# SCH003.net
KiCad netlist of a schematic drawn in Altium Designer
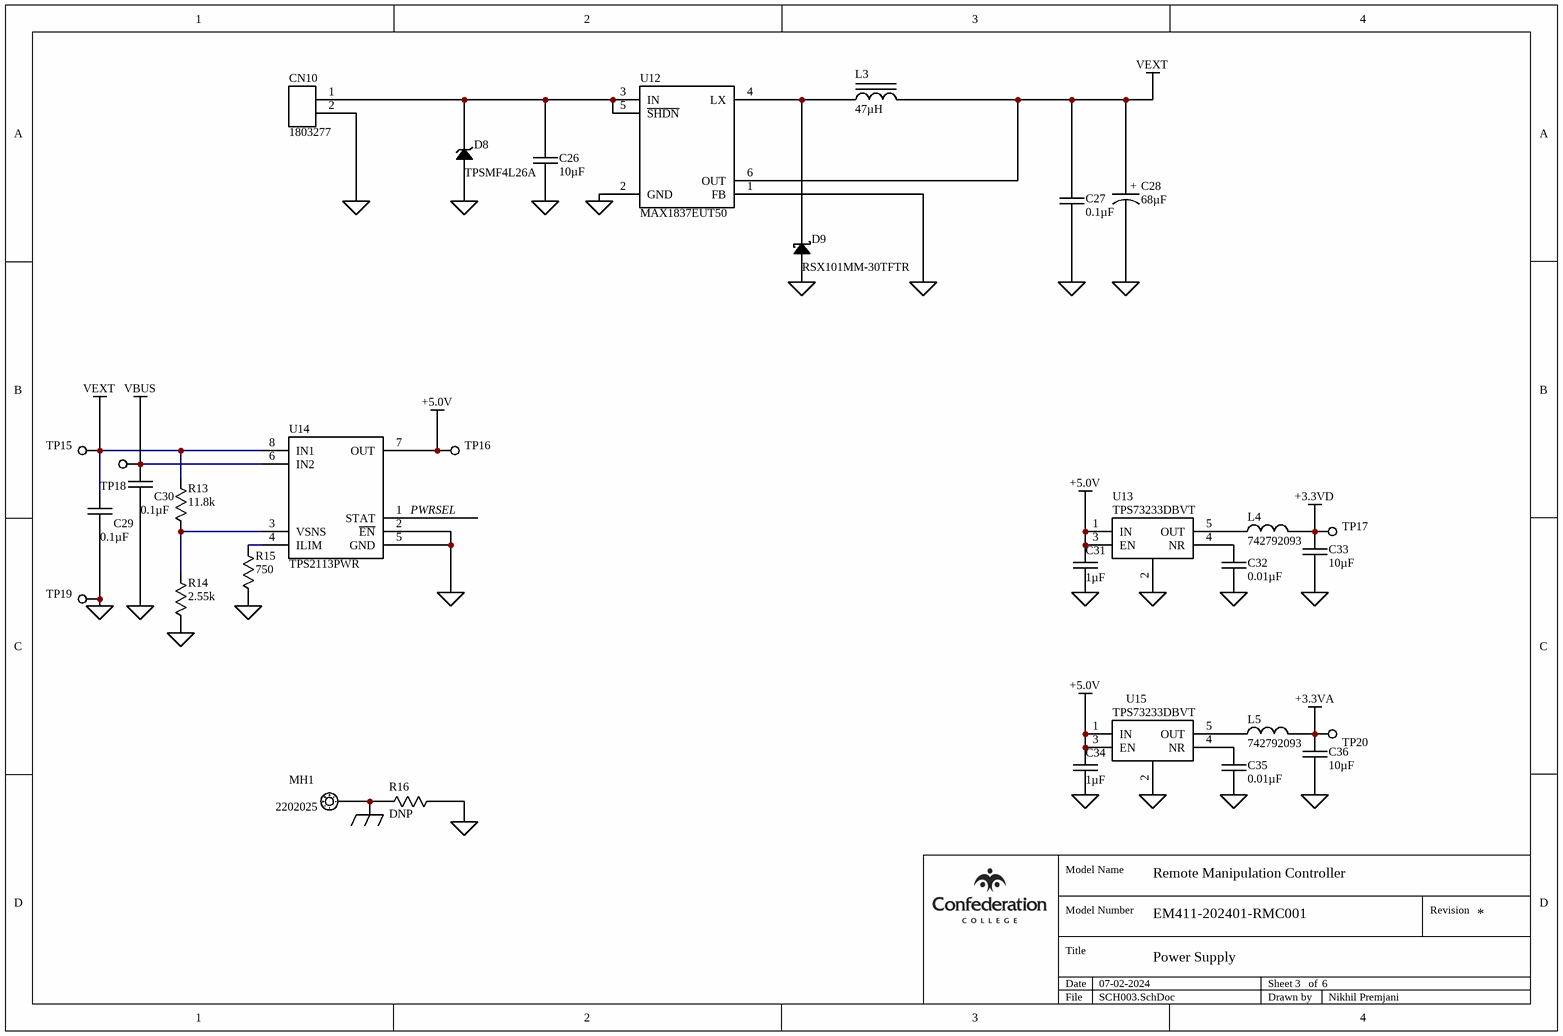
[diagram p0: SCH003.SchDoc]

(export (version "E")
  (design (tool "Eeschema 10.0.6"))
  (components
    (comp (ref "C26")
      (value "10µF")
      (footprint "CAPC2012X14N")
      (description "10µF/25V 10% X5R Multi-Layer Ceramic Capacitor")
      (fields
        (field (name "MANUFACTURER") "Samsung Electro-Mechanics")
        (field (name "PARTNUMBER") "CL21A106KAFN3NE")
      )
      (libsource (lib "EM411-202401-RMC001-000-20240213-T10") (part "CL21A106KAFN3NE"))
    )
    (comp (ref "C27")
      (value "0.1µF")
      (footprint "CAPC2012X14N")
      (description "0.1µF/50V/±10% X7R Ceramic Chip Capacitor")
      (fields (field (name "MANUFACTURER") "Taiyo Yuden") (field (name "PARTNUMBER") "UMK212B7104KGHT"))
      (libsource (lib "EM411-202401-RMC001-001") (part "UMK212B7104KGHT"))
    )
    (comp (ref "C28")
      (value "68µF")
      (footprint "CAPAE7366X60M")
      (description "68µF/10V/20% SMD Aluminum Conductive Polymer Electrolytic Capacitor")
      (fields (field (name "MANUFACTURER") "AVX") (field (name "PARTNUMBER") "APA0606680M010R"))
      (libsource (lib "EM411-202401-RMC001-000-20240213-T10") (part "APA0606680M010R"))
    )
    (comp (ref "C29")
      (value "0.1µF")
      (footprint "CAPC2012X14N")
      (description "0.1µF/50V/±10% X7R Ceramic Chip Capacitor")
      (fields (field (name "MANUFACTURER") "Taiyo Yuden") (field (name "PARTNUMBER") "UMK212B7104KGHT"))
      (libsource (lib "EM411-202401-RMC001-000-20240206") (part "UMK212B7104KGHT"))
    )
    (comp (ref "C30")
      (value "0.1µF")
      (footprint "CAPC2012X14N")
      (description "0.1µF/50V/±10% X7R Ceramic Chip Capacitor")
      (fields (field (name "MANUFACTURER") "Taiyo Yuden") (field (name "PARTNUMBER") "UMK212B7104KGHT"))
      (libsource (lib "EM411-202401-RMC001-000-20240206") (part "UMK212B7104KGHT"))
    )
    (comp (ref "C31")
      (value "1µF")
      (footprint "CAPC2012X14N")
      (description "1µF/50V/±10% X7R Ceramic Chip Capacitor")
      (fields
        (field (name "MANUFACTURER") "Samsung Electro-Mechanics")
        (field (name "PARTNUMBER") "CL21B105KBFNNNG")
      )
      (libsource (lib "EM411-202401-RMC001-001") (part "CL21B105KBFNNNG"))
    )
    (comp (ref "C32")
      (value "0.01µF")
      (footprint "CAPC2012X08N")
      (description "0.01µF/50V/±10% X7R Ceramic Chip Capacitor")
      (fields
        (field (name "MANUFACTURER") "Samsung Electro-Mechanics")
        (field (name "PARTNUMBER") "CL21B103KBANNNC")
      )
      (libsource (lib "EM411-202401-RMC001-001") (part "CL21B103KBANNNC"))
    )
    (comp (ref "C33")
      (value "10µF")
      (footprint "CAPC2012X14N")
      (description "10µF/25V 10% X5R Multi-Layer Ceramic Capacitor")
      (fields
        (field (name "MANUFACTURER") "Samsung Electro-Mechanics")
        (field (name "PARTNUMBER") "CL21A106KAFN3NE")
      )
      (libsource (lib "EM411-202401-RMC001-000-20240213-T10") (part "CL21A106KAFN3NE"))
    )
    (comp (ref "C34")
      (value "1µF")
      (footprint "CAPC2012X14N")
      (description "1µF/50V/±10% X7R Ceramic Chip Capacitor")
      (fields
        (field (name "MANUFACTURER") "Samsung Electro-Mechanics")
        (field (name "PARTNUMBER") "CL21B105KBFNNNG")
      )
      (libsource (lib "EM411-202401-RMC001-001") (part "CL21B105KBFNNNG"))
    )
    (comp (ref "C35")
      (value "0.01µF")
      (footprint "CAPC2012X08N")
      (description "0.01µF/50V/±10% X7R Ceramic Chip Capacitor")
      (fields
        (field (name "MANUFACTURER") "Samsung Electro-Mechanics")
        (field (name "PARTNUMBER") "CL21B103KBANNNC")
      )
      (libsource (lib "EM411-202401-RMC001-001") (part "CL21B103KBANNNC"))
    )
    (comp (ref "C36")
      (value "10µF")
      (footprint "CAPC2012X14N")
      (description "10µF/25V 10% X5R Multi-Layer Ceramic Capacitor")
      (fields
        (field (name "MANUFACTURER") "Samsung Electro-Mechanics")
        (field (name "PARTNUMBER") "CL21A106KAFN3NE")
      )
      (libsource (lib "EM411-202401-RMC001-000-20240213-T10") (part "CL21A106KAFN3NE"))
    )
    (comp (ref "CN10")
      (value "1803277")
      (footprint "PHOENIX_1803277")
      (description "MC 1,5/2G-3,81 Pluggable Terminal Block 2 Pos 3.81mm pitch Through Hole Header")
      (fields (field (name "MANUFACTURER") "Phoenix Contact"))
      (libsource (lib "EM411-202401-RMC001-000-20240213-T10") (part "1803277"))
    )
    (comp (ref "D8")
      (value "TPSMF4L26A")
      (footprint "SODFL370X108-2N")
      (description "TVS Diode")
      (fields (field (name "MANUFACTURER") "Littelfuse"))
      (libsource (lib "EM411-202401-RMC001-000-20240213-T10") (part "TPSMF4L26A"))
    )
    (comp (ref "D9")
      (value "RSX101MM-30TFTR")
      (footprint "SODFL350X90-2N")
      (description "Schottky Barrier Diode")
      (fields (field (name "MANUFACTURER") "Rohm Semiconductor"))
      (libsource (lib "EM411-202401-RMC001-001") (part "RSX101MM-30TFTR"))
    )
    (comp (ref "L3")
      (value "47µH")
      (footprint "INDP102102X40N")
      (description "47µH Shielded Power Inductor")
      (fields (field (name "PARTNUMBER") "MSS1038-473MLC") (field (name "MANUFACTURER") "Coilcraft"))
      (libsource (lib "EM411-202401-RMC001-001") (part "MSS1038-473MLC"))
    )
    (comp (ref "L4")
      (value "742792093")
      (footprint "INDC2012X11N")
      (description "Multilayer SMD Ferrite")
      (fields (field (name "MANUFACTURER") "Wurth Elektronik"))
      (libsource (lib "EM411-202401-RMC001-001") (part "742792093"))
    )
    (comp (ref "L5")
      (value "742792093")
      (footprint "INDC2012X11N")
      (description "Multilayer SMD Ferrite")
      (fields (field (name "MANUFACTURER") "Wurth Elektronik"))
      (libsource (lib "EM411-202401-RMC001-001") (part "742792093"))
    )
    (comp (ref "MH1")
      (value "2202025")
      (footprint "PHOENIX_2202025")
      (description "UM-BASIC/PRO PE CONTACT L1")
      (fields (field (name "MANUFACTURER") "Phoenix Contact"))
      (libsource (lib "EM411-202401-RMC001-001") (part "2202025"))
    )
    (comp (ref "R13")
      (value "11.8k")
      (footprint "RESC2012X06N")
      (description "11.8k, 1%, 0.125W Thick Film Chip Resistor")
      (fields (field (name "MANUFACTURER") "Bourns") (field (name "PARTNUMBER") "CR0805-FX-1182ELF"))
      (libsource (lib "EM411-202401-RMC001-000-20240213-T10") (part "CR0805-FX-1182ELF"))
    )
    (comp (ref "R14")
      (value "2.55k")
      (footprint "RESC2012X06N")
      (description "2.55k, 1%, 0.125W Thick Film Chip Resistor")
      (fields (field (name "MANUFACTURER") "Bourns") (field (name "PARTNUMBER") "CR0805-FX-2551ELF"))
      (libsource (lib "EM411-202401-RMC001-000-20240206") (part "CR0805-FX-2551ELF"))
    )
    (comp (ref "R15")
      (value "750")
      (footprint "RESC2012X06N")
      (description "750, 1%, 0.125W Thick Film Chip Resistor")
      (fields (field (name "MANUFACTURER") "Bourns") (field (name "PARTNUMBER") "CR0805-FX-7500ELF"))
      (libsource (lib "EM411-202401-RMC001-000-20240206") (part "CR0805-FX-7500ELF"))
    )
    (comp (ref "R16")
      (value "DNP")
      (footprint "RESC2012X06N")
      (description "Placeholder for 2012 Resistor")
      (fields (field (name "MANUFACTURER") "Confederation College") (field (name "PARTNUMBER") "DNP2012RES"))
      (libsource (lib "EM411-202401-RMC001-001") (part "DNP2012RES"))
    )
    (comp (ref "TP15")
      (value "Test Point")
      (footprint "TP100")
      (description "Test Point, Surface Mount, 3 mm")
      (fields (field (name "MANUFACTURER") "Confederation College"))
      (libsource (lib "EM411-202401-RMC001-000-20240213-T10") (part "TP3"))
    )
    (comp (ref "TP16")
      (value "Test Point")
      (footprint "TP100")
      (description "Test Point, Surface Mount, 3 mm")
      (fields (field (name "MANUFACTURER") "Confederation College"))
      (libsource (lib "EM411-202401-RMC001-000-20240213-T10") (part "TP3"))
    )
    (comp (ref "TP17")
      (value "Test Point")
      (footprint "TP100")
      (description "Test Point, Surface Mount, 3 mm")
      (fields (field (name "MANUFACTURER") "Confederation College"))
      (libsource (lib "EM411-202401-RMC001-000-20240213-T10") (part "TP3"))
    )
    (comp (ref "TP18")
      (value "Test Point")
      (footprint "TP100")
      (description "Test Point, Surface Mount, 3 mm")
      (fields (field (name "MANUFACTURER") "Confederation College"))
      (libsource (lib "EM411-202401-RMC001-000-20240213-T10") (part "TP3"))
    )
    (comp (ref "TP19")
      (value "Test Point")
      (footprint "TP100")
      (description "Test Point, Surface Mount, 3 mm")
      (fields (field (name "MANUFACTURER") "Confederation College"))
      (libsource (lib "EM411-202401-RMC001-000-20240213-T10") (part "TP3"))
    )
    (comp (ref "TP20")
      (value "Test Point")
      (footprint "TP100")
      (description "Test Point, Surface Mount, 3 mm")
      (fields (field (name "MANUFACTURER") "Confederation College"))
      (libsource (lib "EM411-202401-RMC001-000-20240213-T10") (part "TP3"))
    )
    (comp (ref "U12")
      (value "MAX1837EUT50")
      (footprint "SOT95P280X145-6N")
      (description "24V Internal Switch, 100% Duty Cycle, Step-Down Converter")
      (fields (field (name "MANUFACTURER") "Maxim Integrated"))
      (libsource (lib "EM411-202401-RMC001-001") (part "MAX1837EUT50"))
    )
    (comp (ref "U13")
      (value "TPS73233DBVT")
      (footprint "SOT95P280X145-5N")
      (description "250 mA, 3.3V Low Dropout Voltage Regulator")
      (fields (field (name "MANUFACTURER") "Texas Instruments"))
      (libsource (lib "EM411-202401-RMC001-000-20240213-T10") (part "TPS73233DBVT"))
    )
    (comp (ref "U14")
      (value "TPS2113PWR")
      (footprint "TSOP65P640X120-8N")
      (description "Autoswitching Power Mux")
      (fields (field (name "MANUFACTURER") "Texas Instruments"))
      (libsource (lib "EM411-202401-RMC001-000-20240213-T10") (part "TPS2113PWR"))
    )
    (comp (ref "U15")
      (value "TPS73233DBVT")
      (footprint "SOT95P280X145-5N")
      (description "250 mA, 3.3V Low Dropout Voltage Regulator")
      (fields (field (name "MANUFACTURER") "Texas Instruments"))
      (libsource (lib "EM411-202401-RMC001-000-20240213-T10") (part "TPS73233DBVT"))
    )
  )
  (nets
    (net (code "1") (name "+3.3VA") (class "Default")
      (node (ref "C36") (pin "1") (pinfunction "1_1") (pintype "passive"))
      (node (ref "L5") (pin "2") (pinfunction "2_2") (pintype "passive"))
      (node (ref "TP20") (pin "1") (pinfunction "1_1") (pintype "passive"))
    )
    (net (code "2") (name "+3.3VD") (class "Default")
      (node (ref "C33") (pin "1") (pinfunction "1_1") (pintype "passive"))
      (node (ref "L4") (pin "2") (pinfunction "2_2") (pintype "passive"))
      (node (ref "TP17") (pin "1") (pinfunction "1_1") (pintype "passive"))
    )
    (net (code "3") (name "+5.0V") (class "Default")
      (node (ref "C31") (pin "1") (pinfunction "1_1") (pintype "passive"))
      (node (ref "C34") (pin "1") (pinfunction "1_1") (pintype "passive"))
      (node (ref "TP16") (pin "1") (pinfunction "1_1") (pintype "passive"))
      (node (ref "U13") (pin "1") (pinfunction "IN_1") (pintype "passive"))
      (node (ref "U13") (pin "3") (pinfunction "EN_3") (pintype "passive"))
      (node (ref "U14") (pin "7") (pinfunction "OUT_7") (pintype "passive"))
      (node (ref "U15") (pin "1") (pinfunction "IN_1") (pintype "passive"))
      (node (ref "U15") (pin "3") (pinfunction "EN_3") (pintype "passive"))
    )
    (net (code "4") (name "/PWRSEL") (class "Default")
      (node (ref "U14") (pin "1") (pinfunction "STAT_1") (pintype "passive"))
    )
    (net (code "5") (name "CHGND") (class "Default")
      (node (ref "MH1") (pin "0") (pintype "passive"))
      (node (ref "R16") (pin "1") (pinfunction "1_1") (pintype "passive"))
    )
    (net (code "6") (name "GND") (class "Default")
      (node (ref "C26") (pin "2") (pinfunction "2_2") (pintype "passive"))
      (node (ref "C27") (pin "2") (pinfunction "2_2") (pintype "passive"))
      (node (ref "C28") (pin "2") (pinfunction "2_2") (pintype "passive"))
      (node (ref "C29") (pin "2") (pinfunction "2_2") (pintype "passive"))
      (node (ref "C30") (pin "2") (pinfunction "2_2") (pintype "passive"))
      (node (ref "C31") (pin "2") (pinfunction "2_2") (pintype "passive"))
      (node (ref "C32") (pin "2") (pinfunction "2_2") (pintype "passive"))
      (node (ref "C33") (pin "2") (pinfunction "2_2") (pintype "passive"))
      (node (ref "C34") (pin "2") (pinfunction "2_2") (pintype "passive"))
      (node (ref "C35") (pin "2") (pinfunction "2_2") (pintype "passive"))
      (node (ref "C36") (pin "2") (pinfunction "2_2") (pintype "passive"))
      (node (ref "CN10") (pin "2") (pinfunction "2_2") (pintype "passive"))
      (node (ref "D8") (pin "A") (pinfunction "A_A") (pintype "passive"))
      (node (ref "D9") (pin "A") (pinfunction "A_A") (pintype "passive"))
      (node (ref "R14") (pin "1") (pinfunction "1_1") (pintype "passive"))
      (node (ref "R15") (pin "1") (pinfunction "1_1") (pintype "passive"))
      (node (ref "R16") (pin "2") (pinfunction "2_2") (pintype "passive"))
      (node (ref "TP19") (pin "1") (pinfunction "1_1") (pintype "passive"))
      (node (ref "U12") (pin "1") (pinfunction "FB_1") (pintype "passive"))
      (node (ref "U12") (pin "2") (pinfunction "GND_2") (pintype "passive"))
      (node (ref "U13") (pin "2") (pinfunction "GND_2") (pintype "passive"))
      (node (ref "U14") (pin "2") (pinfunction "~{EN}_2") (pintype "passive"))
      (node (ref "U14") (pin "5") (pinfunction "GND_5") (pintype "passive"))
      (node (ref "U15") (pin "2") (pinfunction "GND_2") (pintype "passive"))
    )
    (net (code "7") (name "Net-(U12-IN)") (class "Default")
      (node (ref "C26") (pin "1") (pinfunction "1_1") (pintype "passive"))
      (node (ref "CN10") (pin "1") (pinfunction "1_1") (pintype "passive"))
      (node (ref "D8") (pin "K") (pinfunction "K_K") (pintype "passive"))
      (node (ref "U12") (pin "3") (pinfunction "IN_3") (pintype "passive"))
      (node (ref "U12") (pin "5") (pinfunction "~{SHDN}_5") (pintype "passive"))
    )
    (net (code "8") (name "Net-(U12-LX)") (class "Default")
      (node (ref "D9") (pin "K") (pinfunction "K_K") (pintype "passive"))
      (node (ref "L3") (pin "2") (pinfunction "2_2") (pintype "passive"))
      (node (ref "U12") (pin "4") (pinfunction "LX_4") (pintype "passive"))
    )
    (net (code "9") (name "Net-(U13-NR)") (class "Default")
      (node (ref "C32") (pin "1") (pinfunction "1_1") (pintype "passive"))
      (node (ref "U13") (pin "4") (pinfunction "NR_4") (pintype "passive"))
    )
    (net (code "10") (name "Net-(U13-OUT)") (class "Default")
      (node (ref "L4") (pin "1") (pinfunction "1_1") (pintype "passive"))
      (node (ref "U13") (pin "5") (pinfunction "OUT_5") (pintype "passive"))
    )
    (net (code "11") (name "Net-(U14-ILIM)") (class "Default")
      (node (ref "R15") (pin "2") (pinfunction "2_2") (pintype "passive"))
      (node (ref "U14") (pin "4") (pinfunction "ILIM_4") (pintype "passive"))
    )
    (net (code "12") (name "Net-(U14-VSNS)") (class "Default")
      (node (ref "R13") (pin "2") (pinfunction "2_2") (pintype "passive"))
      (node (ref "R14") (pin "2") (pinfunction "2_2") (pintype "passive"))
      (node (ref "U14") (pin "3") (pinfunction "VSNS_3") (pintype "passive"))
    )
    (net (code "13") (name "Net-(U15-NR)") (class "Default")
      (node (ref "C35") (pin "1") (pinfunction "1_1") (pintype "passive"))
      (node (ref "U15") (pin "4") (pinfunction "NR_4") (pintype "passive"))
    )
    (net (code "14") (name "Net-(U15-OUT)") (class "Default")
      (node (ref "L5") (pin "1") (pinfunction "1_1") (pintype "passive"))
      (node (ref "U15") (pin "5") (pinfunction "OUT_5") (pintype "passive"))
    )
    (net (code "15") (name "VBUS") (class "Default")
      (node (ref "C30") (pin "1") (pinfunction "1_1") (pintype "passive"))
      (node (ref "TP18") (pin "1") (pinfunction "1_1") (pintype "passive"))
      (node (ref "U14") (pin "6") (pinfunction "IN2_6") (pintype "passive"))
    )
    (net (code "16") (name "VEXT") (class "Default")
      (node (ref "C27") (pin "1") (pinfunction "1_1") (pintype "passive"))
      (node (ref "C28") (pin "1") (pinfunction "1_1") (pintype "passive"))
      (node (ref "C29") (pin "1") (pinfunction "1_1") (pintype "passive"))
      (node (ref "L3") (pin "1") (pinfunction "1_1") (pintype "passive"))
      (node (ref "R13") (pin "1") (pinfunction "1_1") (pintype "passive"))
      (node (ref "TP15") (pin "1") (pinfunction "1_1") (pintype "passive"))
      (node (ref "U12") (pin "6") (pinfunction "OUT_6") (pintype "passive"))
      (node (ref "U14") (pin "8") (pinfunction "IN1_8") (pintype "passive"))
    )
  )
)
